# 20170628-03.net
KiCad netlist of a schematic drawn in EAGLE
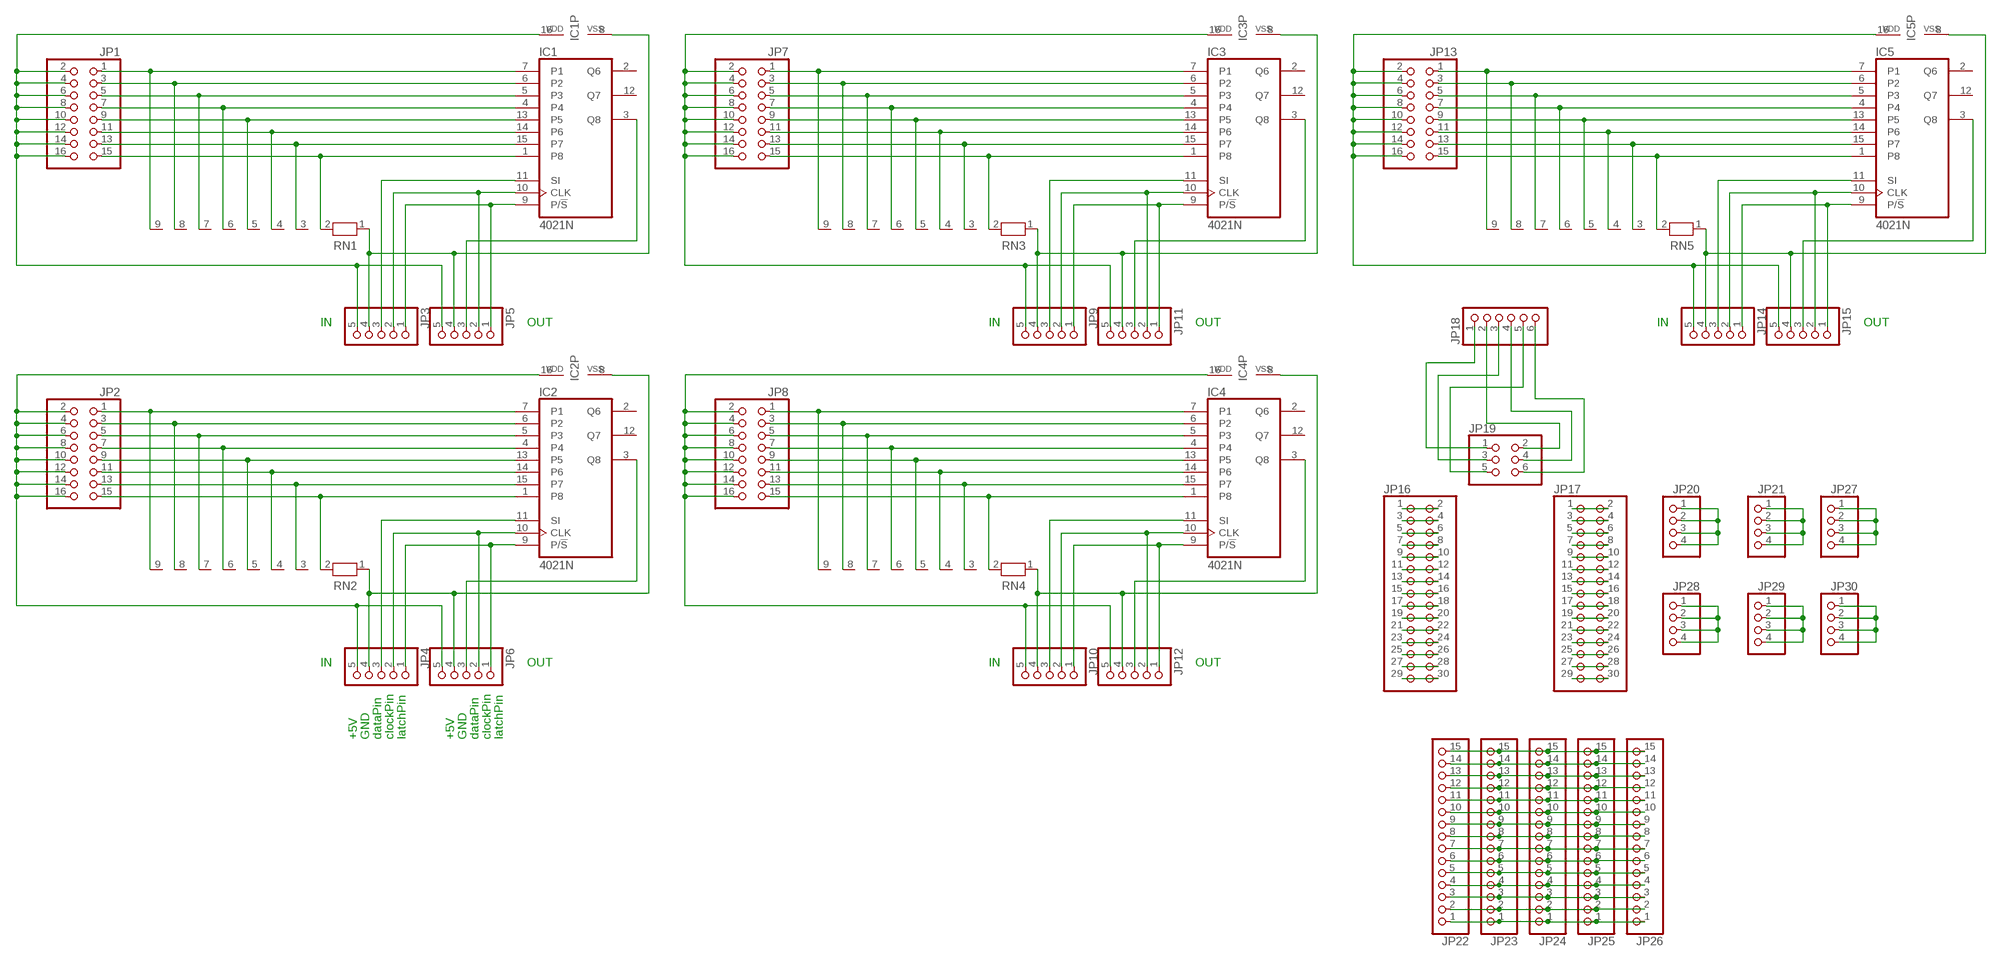
[diagram p0: schematic, sheet 1]

(export (version "E")
  (design (tool "Eeschema 10.0.6"))
  (components
    (comp (ref "IC1")
      (value "4021N")
      (footprint "eagle-import:DIL16")
      (libsource (lib "eagle-import") (part "4021N"))
    )
    (comp (ref "IC2")
      (value "4021N")
      (footprint "eagle-import:DIL16")
      (libsource (lib "eagle-import") (part "4021N"))
    )
    (comp (ref "IC3")
      (value "4021N")
      (footprint "eagle-import:DIL16")
      (libsource (lib "eagle-import") (part "4021N"))
    )
    (comp (ref "IC4")
      (value "4021N")
      (footprint "eagle-import:DIL16")
      (libsource (lib "eagle-import") (part "4021N"))
    )
    (comp (ref "IC5")
      (value "4021N")
      (footprint "eagle-import:DIL16")
      (libsource (lib "eagle-import") (part "4021N"))
    )
    (comp (ref "JP1")
      (value "PINHD-2X8")
      (footprint "eagle-import:2X08")
      (libsource (lib "eagle-import") (part "PINHD-2X8"))
    )
    (comp (ref "JP2")
      (value "PINHD-2X8")
      (footprint "eagle-import:2X08")
      (libsource (lib "eagle-import") (part "PINHD-2X8"))
    )
    (comp (ref "JP3")
      (value "PINHD-1X5")
      (footprint "eagle-import:1X05")
      (libsource (lib "eagle-import") (part "PINHD-1X5"))
    )
    (comp (ref "JP4")
      (value "PINHD-1X5")
      (footprint "eagle-import:1X05")
      (libsource (lib "eagle-import") (part "PINHD-1X5"))
    )
    (comp (ref "JP5")
      (value "PINHD-1X5")
      (footprint "eagle-import:1X05")
      (libsource (lib "eagle-import") (part "PINHD-1X5"))
    )
    (comp (ref "JP6")
      (value "PINHD-1X5")
      (footprint "eagle-import:1X05")
      (libsource (lib "eagle-import") (part "PINHD-1X5"))
    )
    (comp (ref "JP7")
      (value "PINHD-2X8")
      (footprint "eagle-import:2X08")
      (libsource (lib "eagle-import") (part "PINHD-2X8"))
    )
    (comp (ref "JP8")
      (value "PINHD-2X8")
      (footprint "eagle-import:2X08")
      (libsource (lib "eagle-import") (part "PINHD-2X8"))
    )
    (comp (ref "JP9")
      (value "PINHD-1X5")
      (footprint "eagle-import:1X05")
      (libsource (lib "eagle-import") (part "PINHD-1X5"))
    )
    (comp (ref "JP10")
      (value "PINHD-1X5")
      (footprint "eagle-import:1X05")
      (libsource (lib "eagle-import") (part "PINHD-1X5"))
    )
    (comp (ref "JP11")
      (value "PINHD-1X5")
      (footprint "eagle-import:1X05")
      (libsource (lib "eagle-import") (part "PINHD-1X5"))
    )
    (comp (ref "JP12")
      (value "PINHD-1X5")
      (footprint "eagle-import:1X05")
      (libsource (lib "eagle-import") (part "PINHD-1X5"))
    )
    (comp (ref "JP13")
      (value "PINHD-2X8")
      (footprint "eagle-import:2X08")
      (libsource (lib "eagle-import") (part "PINHD-2X8"))
    )
    (comp (ref "JP14")
      (value "PINHD-1X5")
      (footprint "eagle-import:1X05")
      (libsource (lib "eagle-import") (part "PINHD-1X5"))
    )
    (comp (ref "JP15")
      (value "PINHD-1X5")
      (footprint "eagle-import:1X05")
      (libsource (lib "eagle-import") (part "PINHD-1X5"))
    )
    (comp (ref "JP16")
      (value "PINHD-2X15")
      (footprint "eagle-import:2X15")
      (libsource (lib "eagle-import") (part "PINHD-2X15"))
    )
    (comp (ref "JP17")
      (value "PINHD-2X15")
      (footprint "eagle-import:2X15")
      (libsource (lib "eagle-import") (part "PINHD-2X15"))
    )
    (comp (ref "JP18")
      (value "PINHD-1X6")
      (footprint "eagle-import:1X06")
      (libsource (lib "eagle-import") (part "PINHD-1X6"))
    )
    (comp (ref "JP19")
      (value "PINHD-2X3")
      (footprint "eagle-import:2X03")
      (libsource (lib "eagle-import") (part "PINHD-2X3"))
    )
    (comp (ref "JP20")
      (value "PINHD-1X4")
      (footprint "eagle-import:1X04")
      (libsource (lib "eagle-import") (part "PINHD-1X4"))
    )
    (comp (ref "JP21")
      (value "PINHD-1X4")
      (footprint "eagle-import:1X04")
      (libsource (lib "eagle-import") (part "PINHD-1X4"))
    )
    (comp (ref "JP22")
      (value "PINHD-1X15")
      (footprint "eagle-import:1X15")
      (libsource (lib "eagle-import") (part "PINHD-1X15"))
    )
    (comp (ref "JP23")
      (value "PINHD-1X15")
      (footprint "eagle-import:1X15")
      (libsource (lib "eagle-import") (part "PINHD-1X15"))
    )
    (comp (ref "JP24")
      (value "PINHD-1X15")
      (footprint "eagle-import:1X15")
      (libsource (lib "eagle-import") (part "PINHD-1X15"))
    )
    (comp (ref "JP25")
      (value "PINHD-1X15")
      (footprint "eagle-import:1X15")
      (libsource (lib "eagle-import") (part "PINHD-1X15"))
    )
    (comp (ref "JP26")
      (value "PINHD-1X15")
      (footprint "eagle-import:1X15")
      (libsource (lib "eagle-import") (part "PINHD-1X15"))
    )
    (comp (ref "JP27")
      (value "PINHD-1X4")
      (footprint "eagle-import:1X04")
      (libsource (lib "eagle-import") (part "PINHD-1X4"))
    )
    (comp (ref "JP28")
      (value "PINHD-1X4")
      (footprint "eagle-import:1X04")
      (libsource (lib "eagle-import") (part "PINHD-1X4"))
    )
    (comp (ref "JP29")
      (value "PINHD-1X4")
      (footprint "eagle-import:1X04")
      (libsource (lib "eagle-import") (part "PINHD-1X4"))
    )
    (comp (ref "JP30")
      (value "PINHD-1X4")
      (footprint "eagle-import:1X04")
      (libsource (lib "eagle-import") (part "PINHD-1X4"))
    )
    (comp (ref "RN1")
      (value "RN08")
      (footprint "eagle-import:RN-9")
      (libsource (lib "eagle-import") (part "RN08"))
    )
    (comp (ref "RN2")
      (value "RN08")
      (footprint "eagle-import:RN-9")
      (libsource (lib "eagle-import") (part "RN08"))
    )
    (comp (ref "RN3")
      (value "RN08")
      (footprint "eagle-import:RN-9")
      (libsource (lib "eagle-import") (part "RN08"))
    )
    (comp (ref "RN4")
      (value "RN08")
      (footprint "eagle-import:RN-9")
      (libsource (lib "eagle-import") (part "RN08"))
    )
    (comp (ref "RN5")
      (value "RN08")
      (footprint "eagle-import:RN-9")
      (libsource (lib "eagle-import") (part "RN08"))
    )
  )
  (nets
    (net (code "1") (name "Net-(IC1A-CLK)") (class "Default")
      (node (ref "IC1") (pin "10") (pinfunction "CLK_10") (pintype "input"))
      (node (ref "JP3") (pin "2") (pinfunction "2_2") (pintype "passive"))
      (node (ref "JP5") (pin "2") (pinfunction "2_2") (pintype "passive"))
    )
    (net (code "2") (name "Net-(IC1A-P1)") (class "Default")
      (node (ref "IC1") (pin "7") (pinfunction "P1_7") (pintype "input"))
      (node (ref "JP1") (pin "1") (pinfunction "1_1") (pintype "passive"))
      (node (ref "RN1") (pin "9") (pinfunction "9_9") (pintype "passive"))
    )
    (net (code "3") (name "Net-(IC1A-P2)") (class "Default")
      (node (ref "IC1") (pin "6") (pinfunction "P2_6") (pintype "input"))
      (node (ref "JP1") (pin "3") (pinfunction "3_3") (pintype "passive"))
      (node (ref "RN1") (pin "8") (pinfunction "8_8") (pintype "passive"))
    )
    (net (code "4") (name "Net-(IC1A-P3)") (class "Default")
      (node (ref "IC1") (pin "5") (pinfunction "P3_5") (pintype "input"))
      (node (ref "JP1") (pin "5") (pinfunction "5_5") (pintype "passive"))
      (node (ref "RN1") (pin "7") (pinfunction "7_7") (pintype "passive"))
    )
    (net (code "5") (name "Net-(IC1A-P4)") (class "Default")
      (node (ref "IC1") (pin "4") (pinfunction "P4_4") (pintype "input"))
      (node (ref "JP1") (pin "7") (pinfunction "7_7") (pintype "passive"))
      (node (ref "RN1") (pin "6") (pinfunction "6_6") (pintype "passive"))
    )
    (net (code "6") (name "Net-(IC1A-P5)") (class "Default")
      (node (ref "IC1") (pin "13") (pinfunction "P5_13") (pintype "input"))
      (node (ref "JP1") (pin "9") (pinfunction "9_9") (pintype "passive"))
      (node (ref "RN1") (pin "5") (pinfunction "5_5") (pintype "passive"))
    )
    (net (code "7") (name "Net-(IC1A-P6)") (class "Default")
      (node (ref "IC1") (pin "14") (pinfunction "P6_14") (pintype "input"))
      (node (ref "JP1") (pin "11") (pinfunction "11_11") (pintype "passive"))
      (node (ref "RN1") (pin "4") (pinfunction "4_4") (pintype "passive"))
    )
    (net (code "8") (name "Net-(IC1A-P7)") (class "Default")
      (node (ref "IC1") (pin "15") (pinfunction "P7_15") (pintype "input"))
      (node (ref "JP1") (pin "13") (pinfunction "13_13") (pintype "passive"))
      (node (ref "RN1") (pin "3") (pinfunction "3_3") (pintype "passive"))
    )
    (net (code "9") (name "Net-(IC1A-P8)") (class "Default")
      (node (ref "IC1") (pin "1") (pinfunction "P8_1") (pintype "input"))
      (node (ref "JP1") (pin "15") (pinfunction "15_15") (pintype "passive"))
      (node (ref "RN1") (pin "2") (pinfunction "2_2") (pintype "passive"))
    )
    (net (code "10") (name "Net-(IC1A-P{slash}~{S})") (class "Default")
      (node (ref "IC1") (pin "9") (pinfunction "P/~{S}_9") (pintype "input"))
      (node (ref "JP3") (pin "1") (pinfunction "1_1") (pintype "passive"))
      (node (ref "JP5") (pin "1") (pinfunction "1_1") (pintype "passive"))
    )
    (net (code "11") (name "Net-(IC1A-Q8)") (class "Default")
      (node (ref "IC1") (pin "3") (pinfunction "Q8_3") (pintype "output"))
      (node (ref "JP5") (pin "3") (pinfunction "3_3") (pintype "passive"))
    )
    (net (code "12") (name "Net-(IC1A-SI)") (class "Default")
      (node (ref "IC1") (pin "11") (pinfunction "SI_11") (pintype "input"))
      (node (ref "JP3") (pin "3") (pinfunction "3_3") (pintype "passive"))
    )
    (net (code "13") (name "Net-(IC1B-VDD)") (class "Default")
      (node (ref "IC1") (pin "16") (pinfunction "VDD_16") (pintype "power_in"))
      (node (ref "JP1") (pin "10") (pinfunction "10_10") (pintype "passive"))
      (node (ref "JP1") (pin "12") (pinfunction "12_12") (pintype "passive"))
      (node (ref "JP1") (pin "14") (pinfunction "14_14") (pintype "passive"))
      (node (ref "JP1") (pin "16") (pinfunction "16_16") (pintype "passive"))
      (node (ref "JP1") (pin "2") (pinfunction "2_2") (pintype "passive"))
      (node (ref "JP1") (pin "4") (pinfunction "4_4") (pintype "passive"))
      (node (ref "JP1") (pin "6") (pinfunction "6_6") (pintype "passive"))
      (node (ref "JP1") (pin "8") (pinfunction "8_8") (pintype "passive"))
      (node (ref "JP3") (pin "5") (pinfunction "5_5") (pintype "passive"))
      (node (ref "JP5") (pin "5") (pinfunction "5_5") (pintype "passive"))
    )
    (net (code "14") (name "Net-(IC1B-VSS)") (class "Default")
      (node (ref "IC1") (pin "8") (pinfunction "VSS_8") (pintype "power_in"))
      (node (ref "JP3") (pin "4") (pinfunction "4_4") (pintype "passive"))
      (node (ref "JP5") (pin "4") (pinfunction "4_4") (pintype "passive"))
      (node (ref "RN1") (pin "1") (pinfunction "1_1") (pintype "passive"))
    )
    (net (code "15") (name "Net-(IC2A-CLK)") (class "Default")
      (node (ref "IC2") (pin "10") (pinfunction "CLK_10") (pintype "input"))
      (node (ref "JP4") (pin "2") (pinfunction "2_2") (pintype "passive"))
      (node (ref "JP6") (pin "2") (pinfunction "2_2") (pintype "passive"))
    )
    (net (code "16") (name "Net-(IC2A-P1)") (class "Default")
      (node (ref "IC2") (pin "7") (pinfunction "P1_7") (pintype "input"))
      (node (ref "JP2") (pin "1") (pinfunction "1_1") (pintype "passive"))
      (node (ref "RN2") (pin "9") (pinfunction "9_9") (pintype "passive"))
    )
    (net (code "17") (name "Net-(IC2A-P2)") (class "Default")
      (node (ref "IC2") (pin "6") (pinfunction "P2_6") (pintype "input"))
      (node (ref "JP2") (pin "3") (pinfunction "3_3") (pintype "passive"))
      (node (ref "RN2") (pin "8") (pinfunction "8_8") (pintype "passive"))
    )
    (net (code "18") (name "Net-(IC2A-P3)") (class "Default")
      (node (ref "IC2") (pin "5") (pinfunction "P3_5") (pintype "input"))
      (node (ref "JP2") (pin "5") (pinfunction "5_5") (pintype "passive"))
      (node (ref "RN2") (pin "7") (pinfunction "7_7") (pintype "passive"))
    )
    (net (code "19") (name "Net-(IC2A-P4)") (class "Default")
      (node (ref "IC2") (pin "4") (pinfunction "P4_4") (pintype "input"))
      (node (ref "JP2") (pin "7") (pinfunction "7_7") (pintype "passive"))
      (node (ref "RN2") (pin "6") (pinfunction "6_6") (pintype "passive"))
    )
    (net (code "20") (name "Net-(IC2A-P5)") (class "Default")
      (node (ref "IC2") (pin "13") (pinfunction "P5_13") (pintype "input"))
      (node (ref "JP2") (pin "9") (pinfunction "9_9") (pintype "passive"))
      (node (ref "RN2") (pin "5") (pinfunction "5_5") (pintype "passive"))
    )
    (net (code "21") (name "Net-(IC2A-P6)") (class "Default")
      (node (ref "IC2") (pin "14") (pinfunction "P6_14") (pintype "input"))
      (node (ref "JP2") (pin "11") (pinfunction "11_11") (pintype "passive"))
      (node (ref "RN2") (pin "4") (pinfunction "4_4") (pintype "passive"))
    )
    (net (code "22") (name "Net-(IC2A-P7)") (class "Default")
      (node (ref "IC2") (pin "15") (pinfunction "P7_15") (pintype "input"))
      (node (ref "JP2") (pin "13") (pinfunction "13_13") (pintype "passive"))
      (node (ref "RN2") (pin "3") (pinfunction "3_3") (pintype "passive"))
    )
    (net (code "23") (name "Net-(IC2A-P8)") (class "Default")
      (node (ref "IC2") (pin "1") (pinfunction "P8_1") (pintype "input"))
      (node (ref "JP2") (pin "15") (pinfunction "15_15") (pintype "passive"))
      (node (ref "RN2") (pin "2") (pinfunction "2_2") (pintype "passive"))
    )
    (net (code "24") (name "Net-(IC2A-P{slash}~{S})") (class "Default")
      (node (ref "IC2") (pin "9") (pinfunction "P/~{S}_9") (pintype "input"))
      (node (ref "JP4") (pin "1") (pinfunction "1_1") (pintype "passive"))
      (node (ref "JP6") (pin "1") (pinfunction "1_1") (pintype "passive"))
    )
    (net (code "25") (name "Net-(IC2A-Q8)") (class "Default")
      (node (ref "IC2") (pin "3") (pinfunction "Q8_3") (pintype "output"))
      (node (ref "JP6") (pin "3") (pinfunction "3_3") (pintype "passive"))
    )
    (net (code "26") (name "Net-(IC2A-SI)") (class "Default")
      (node (ref "IC2") (pin "11") (pinfunction "SI_11") (pintype "input"))
      (node (ref "JP4") (pin "3") (pinfunction "3_3") (pintype "passive"))
    )
    (net (code "27") (name "Net-(IC2B-VDD)") (class "Default")
      (node (ref "IC2") (pin "16") (pinfunction "VDD_16") (pintype "power_in"))
      (node (ref "JP2") (pin "10") (pinfunction "10_10") (pintype "passive"))
      (node (ref "JP2") (pin "12") (pinfunction "12_12") (pintype "passive"))
      (node (ref "JP2") (pin "14") (pinfunction "14_14") (pintype "passive"))
      (node (ref "JP2") (pin "16") (pinfunction "16_16") (pintype "passive"))
      (node (ref "JP2") (pin "2") (pinfunction "2_2") (pintype "passive"))
      (node (ref "JP2") (pin "4") (pinfunction "4_4") (pintype "passive"))
      (node (ref "JP2") (pin "6") (pinfunction "6_6") (pintype "passive"))
      (node (ref "JP2") (pin "8") (pinfunction "8_8") (pintype "passive"))
      (node (ref "JP4") (pin "5") (pinfunction "5_5") (pintype "passive"))
      (node (ref "JP6") (pin "5") (pinfunction "5_5") (pintype "passive"))
    )
    (net (code "28") (name "Net-(IC2B-VSS)") (class "Default")
      (node (ref "IC2") (pin "8") (pinfunction "VSS_8") (pintype "power_in"))
      (node (ref "JP4") (pin "4") (pinfunction "4_4") (pintype "passive"))
      (node (ref "JP6") (pin "4") (pinfunction "4_4") (pintype "passive"))
      (node (ref "RN2") (pin "1") (pinfunction "1_1") (pintype "passive"))
    )
    (net (code "29") (name "Net-(IC3A-CLK)") (class "Default")
      (node (ref "IC3") (pin "10") (pinfunction "CLK_10") (pintype "input"))
      (node (ref "JP11") (pin "2") (pinfunction "2_2") (pintype "passive"))
      (node (ref "JP9") (pin "2") (pinfunction "2_2") (pintype "passive"))
    )
    (net (code "30") (name "Net-(IC3A-P1)") (class "Default")
      (node (ref "IC3") (pin "7") (pinfunction "P1_7") (pintype "input"))
      (node (ref "JP7") (pin "1") (pinfunction "1_1") (pintype "passive"))
      (node (ref "RN3") (pin "9") (pinfunction "9_9") (pintype "passive"))
    )
    (net (code "31") (name "Net-(IC3A-P2)") (class "Default")
      (node (ref "IC3") (pin "6") (pinfunction "P2_6") (pintype "input"))
      (node (ref "JP7") (pin "3") (pinfunction "3_3") (pintype "passive"))
      (node (ref "RN3") (pin "8") (pinfunction "8_8") (pintype "passive"))
    )
    (net (code "32") (name "Net-(IC3A-P3)") (class "Default")
      (node (ref "IC3") (pin "5") (pinfunction "P3_5") (pintype "input"))
      (node (ref "JP7") (pin "5") (pinfunction "5_5") (pintype "passive"))
      (node (ref "RN3") (pin "7") (pinfunction "7_7") (pintype "passive"))
    )
    (net (code "33") (name "Net-(IC3A-P4)") (class "Default")
      (node (ref "IC3") (pin "4") (pinfunction "P4_4") (pintype "input"))
      (node (ref "JP7") (pin "7") (pinfunction "7_7") (pintype "passive"))
      (node (ref "RN3") (pin "6") (pinfunction "6_6") (pintype "passive"))
    )
    (net (code "34") (name "Net-(IC3A-P5)") (class "Default")
      (node (ref "IC3") (pin "13") (pinfunction "P5_13") (pintype "input"))
      (node (ref "JP7") (pin "9") (pinfunction "9_9") (pintype "passive"))
      (node (ref "RN3") (pin "5") (pinfunction "5_5") (pintype "passive"))
    )
    (net (code "35") (name "Net-(IC3A-P6)") (class "Default")
      (node (ref "IC3") (pin "14") (pinfunction "P6_14") (pintype "input"))
      (node (ref "JP7") (pin "11") (pinfunction "11_11") (pintype "passive"))
      (node (ref "RN3") (pin "4") (pinfunction "4_4") (pintype "passive"))
    )
    (net (code "36") (name "Net-(IC3A-P7)") (class "Default")
      (node (ref "IC3") (pin "15") (pinfunction "P7_15") (pintype "input"))
      (node (ref "JP7") (pin "13") (pinfunction "13_13") (pintype "passive"))
      (node (ref "RN3") (pin "3") (pinfunction "3_3") (pintype "passive"))
    )
    (net (code "37") (name "Net-(IC3A-P8)") (class "Default")
      (node (ref "IC3") (pin "1") (pinfunction "P8_1") (pintype "input"))
      (node (ref "JP7") (pin "15") (pinfunction "15_15") (pintype "passive"))
      (node (ref "RN3") (pin "2") (pinfunction "2_2") (pintype "passive"))
    )
    (net (code "38") (name "Net-(IC3A-P{slash}~{S})") (class "Default")
      (node (ref "IC3") (pin "9") (pinfunction "P/~{S}_9") (pintype "input"))
      (node (ref "JP11") (pin "1") (pinfunction "1_1") (pintype "passive"))
      (node (ref "JP9") (pin "1") (pinfunction "1_1") (pintype "passive"))
    )
    (net (code "39") (name "Net-(IC3A-Q8)") (class "Default")
      (node (ref "IC3") (pin "3") (pinfunction "Q8_3") (pintype "output"))
      (node (ref "JP11") (pin "3") (pinfunction "3_3") (pintype "passive"))
    )
    (net (code "40") (name "Net-(IC3A-SI)") (class "Default")
      (node (ref "IC3") (pin "11") (pinfunction "SI_11") (pintype "input"))
      (node (ref "JP9") (pin "3") (pinfunction "3_3") (pintype "passive"))
    )
    (net (code "41") (name "Net-(IC3B-VDD)") (class "Default")
      (node (ref "IC3") (pin "16") (pinfunction "VDD_16") (pintype "power_in"))
      (node (ref "JP11") (pin "5") (pinfunction "5_5") (pintype "passive"))
      (node (ref "JP7") (pin "10") (pinfunction "10_10") (pintype "passive"))
      (node (ref "JP7") (pin "12") (pinfunction "12_12") (pintype "passive"))
      (node (ref "JP7") (pin "14") (pinfunction "14_14") (pintype "passive"))
      (node (ref "JP7") (pin "16") (pinfunction "16_16") (pintype "passive"))
      (node (ref "JP7") (pin "2") (pinfunction "2_2") (pintype "passive"))
      (node (ref "JP7") (pin "4") (pinfunction "4_4") (pintype "passive"))
      (node (ref "JP7") (pin "6") (pinfunction "6_6") (pintype "passive"))
      (node (ref "JP7") (pin "8") (pinfunction "8_8") (pintype "passive"))
      (node (ref "JP9") (pin "5") (pinfunction "5_5") (pintype "passive"))
    )
    (net (code "42") (name "Net-(IC3B-VSS)") (class "Default")
      (node (ref "IC3") (pin "8") (pinfunction "VSS_8") (pintype "power_in"))
      (node (ref "JP11") (pin "4") (pinfunction "4_4") (pintype "passive"))
      (node (ref "JP9") (pin "4") (pinfunction "4_4") (pintype "passive"))
      (node (ref "RN3") (pin "1") (pinfunction "1_1") (pintype "passive"))
    )
    (net (code "43") (name "Net-(IC4A-CLK)") (class "Default")
      (node (ref "IC4") (pin "10") (pinfunction "CLK_10") (pintype "input"))
      (node (ref "JP10") (pin "2") (pinfunction "2_2") (pintype "passive"))
      (node (ref "JP12") (pin "2") (pinfunction "2_2") (pintype "passive"))
    )
    (net (code "44") (name "Net-(IC4A-P1)") (class "Default")
      (node (ref "IC4") (pin "7") (pinfunction "P1_7") (pintype "input"))
      (node (ref "JP8") (pin "1") (pinfunction "1_1") (pintype "passive"))
      (node (ref "RN4") (pin "9") (pinfunction "9_9") (pintype "passive"))
    )
    (net (code "45") (name "Net-(IC4A-P2)") (class "Default")
      (node (ref "IC4") (pin "6") (pinfunction "P2_6") (pintype "input"))
      (node (ref "JP8") (pin "3") (pinfunction "3_3") (pintype "passive"))
      (node (ref "RN4") (pin "8") (pinfunction "8_8") (pintype "passive"))
    )
    (net (code "46") (name "Net-(IC4A-P3)") (class "Default")
      (node (ref "IC4") (pin "5") (pinfunction "P3_5") (pintype "input"))
      (node (ref "JP8") (pin "5") (pinfunction "5_5") (pintype "passive"))
      (node (ref "RN4") (pin "7") (pinfunction "7_7") (pintype "passive"))
    )
    (net (code "47") (name "Net-(IC4A-P4)") (class "Default")
      (node (ref "IC4") (pin "4") (pinfunction "P4_4") (pintype "input"))
      (node (ref "JP8") (pin "7") (pinfunction "7_7") (pintype "passive"))
      (node (ref "RN4") (pin "6") (pinfunction "6_6") (pintype "passive"))
    )
    (net (code "48") (name "Net-(IC4A-P5)") (class "Default")
      (node (ref "IC4") (pin "13") (pinfunction "P5_13") (pintype "input"))
      (node (ref "JP8") (pin "9") (pinfunction "9_9") (pintype "passive"))
      (node (ref "RN4") (pin "5") (pinfunction "5_5") (pintype "passive"))
    )
    (net (code "49") (name "Net-(IC4A-P6)") (class "Default")
      (node (ref "IC4") (pin "14") (pinfunction "P6_14") (pintype "input"))
      (node (ref "JP8") (pin "11") (pinfunction "11_11") (pintype "passive"))
      (node (ref "RN4") (pin "4") (pinfunction "4_4") (pintype "passive"))
    )
    (net (code "50") (name "Net-(IC4A-P7)") (class "Default")
      (node (ref "IC4") (pin "15") (pinfunction "P7_15") (pintype "input"))
      (node (ref "JP8") (pin "13") (pinfunction "13_13") (pintype "passive"))
      (node (ref "RN4") (pin "3") (pinfunction "3_3") (pintype "passive"))
    )
    (net (code "51") (name "Net-(IC4A-P8)") (class "Default")
      (node (ref "IC4") (pin "1") (pinfunction "P8_1") (pintype "input"))
      (node (ref "JP8") (pin "15") (pinfunction "15_15") (pintype "passive"))
      (node (ref "RN4") (pin "2") (pinfunction "2_2") (pintype "passive"))
    )
    (net (code "52") (name "Net-(IC4A-P{slash}~{S})") (class "Default")
      (node (ref "IC4") (pin "9") (pinfunction "P/~{S}_9") (pintype "input"))
      (node (ref "JP10") (pin "1") (pinfunction "1_1") (pintype "passive"))
      (node (ref "JP12") (pin "1") (pinfunction "1_1") (pintype "passive"))
    )
    (net (code "53") (name "Net-(IC4A-Q8)") (class "Default")
      (node (ref "IC4") (pin "3") (pinfunction "Q8_3") (pintype "output"))
      (node (ref "JP12") (pin "3") (pinfunction "3_3") (pintype "passive"))
    )
    (net (code "54") (name "Net-(IC4A-SI)") (class "Default")
      (node (ref "IC4") (pin "11") (pinfunction "SI_11") (pintype "input"))
      (node (ref "JP10") (pin "3") (pinfunction "3_3") (pintype "passive"))
    )
    (net (code "55") (name "Net-(IC4B-VDD)") (class "Default")
      (node (ref "IC4") (pin "16") (pinfunction "VDD_16") (pintype "power_in"))
      (node (ref "JP10") (pin "5") (pinfunction "5_5") (pintype "passive"))
      (node (ref "JP12") (pin "5") (pinfunction "5_5") (pintype "passive"))
      (node (ref "JP8") (pin "10") (pinfunction "10_10") (pintype "passive"))
      (node (ref "JP8") (pin "12") (pinfunction "12_12") (pintype "passive"))
      (node (ref "JP8") (pin "14") (pinfunction "14_14") (pintype "passive"))
      (node (ref "JP8") (pin "16") (pinfunction "16_16") (pintype "passive"))
      (node (ref "JP8") (pin "2") (pinfunction "2_2") (pintype "passive"))
      (node (ref "JP8") (pin "4") (pinfunction "4_4") (pintype "passive"))
      (node (ref "JP8") (pin "6") (pinfunction "6_6") (pintype "passive"))
      (node (ref "JP8") (pin "8") (pinfunction "8_8") (pintype "passive"))
    )
    (net (code "56") (name "Net-(IC4B-VSS)") (class "Default")
      (node (ref "IC4") (pin "8") (pinfunction "VSS_8") (pintype "power_in"))
      (node (ref "JP10") (pin "4") (pinfunction "4_4") (pintype "passive"))
      (node (ref "JP12") (pin "4") (pinfunction "4_4") (pintype "passive"))
      (node (ref "RN4") (pin "1") (pinfunction "1_1") (pintype "passive"))
    )
    (net (code "57") (name "Net-(IC5A-CLK)") (class "Default")
      (node (ref "IC5") (pin "10") (pinfunction "CLK_10") (pintype "input"))
      (node (ref "JP14") (pin "2") (pinfunction "2_2") (pintype "passive"))
      (node (ref "JP15") (pin "2") (pinfunction "2_2") (pintype "passive"))
    )
    (net (code "58") (name "Net-(IC5A-P1)") (class "Default")
      (node (ref "IC5") (pin "7") (pinfunction "P1_7") (pintype "input"))
      (node (ref "JP13") (pin "1") (pinfunction "1_1") (pintype "passive"))
      (node (ref "RN5") (pin "9") (pinfunction "9_9") (pintype "passive"))
    )
    (net (code "59") (name "Net-(IC5A-P2)") (class "Default")
      (node (ref "IC5") (pin "6") (pinfunction "P2_6") (pintype "input"))
      (node (ref "JP13") (pin "3") (pinfunction "3_3") (pintype "passive"))
      (node (ref "RN5") (pin "8") (pinfunction "8_8") (pintype "passive"))
    )
    (net (code "60") (name "Net-(IC5A-P3)") (class "Default")
      (node (ref "IC5") (pin "5") (pinfunction "P3_5") (pintype "input"))
      (node (ref "JP13") (pin "5") (pinfunction "5_5") (pintype "passive"))
      (node (ref "RN5") (pin "7") (pinfunction "7_7") (pintype "passive"))
    )
    (net (code "61") (name "Net-(IC5A-P4)") (class "Default")
      (node (ref "IC5") (pin "4") (pinfunction "P4_4") (pintype "input"))
      (node (ref "JP13") (pin "7") (pinfunction "7_7") (pintype "passive"))
      (node (ref "RN5") (pin "6") (pinfunction "6_6") (pintype "passive"))
    )
    (net (code "62") (name "Net-(IC5A-P5)") (class "Default")
      (node (ref "IC5") (pin "13") (pinfunction "P5_13") (pintype "input"))
      (node (ref "JP13") (pin "9") (pinfunction "9_9") (pintype "passive"))
      (node (ref "RN5") (pin "5") (pinfunction "5_5") (pintype "passive"))
    )
    (net (code "63") (name "Net-(IC5A-P6)") (class "Default")
      (node (ref "IC5") (pin "14") (pinfunction "P6_14") (pintype "input"))
      (node (ref "JP13") (pin "11") (pinfunction "11_11") (pintype "passive"))
      (node (ref "RN5") (pin "4") (pinfunction "4_4") (pintype "passive"))
    )
    (net (code "64") (name "Net-(IC5A-P7)") (class "Default")
      (node (ref "IC5") (pin "15") (pinfunction "P7_15") (pintype "input"))
      (node (ref "JP13") (pin "13") (pinfunction "13_13") (pintype "passive"))
      (node (ref "RN5") (pin "3") (pinfunction "3_3") (pintype "passive"))
    )
    (net (code "65") (name "Net-(IC5A-P8)") (class "Default")
      (node (ref "IC5") (pin "1") (pinfunction "P8_1") (pintype "input"))
      (node (ref "JP13") (pin "15") (pinfunction "15_15") (pintype "passive"))
      (node (ref "RN5") (pin "2") (pinfunction "2_2") (pintype "passive"))
    )
    (net (code "66") (name "Net-(IC5A-P{slash}~{S})") (class "Default")
      (node (ref "IC5") (pin "9") (pinfunction "P/~{S}_9") (pintype "input"))
      (node (ref "JP14") (pin "1") (pinfunction "1_1") (pintype "passive"))
      (node (ref "JP15") (pin "1") (pinfunction "1_1") (pintype "passive"))
    )
    (net (code "67") (name "Net-(IC5A-Q8)") (class "Default")
      (node (ref "IC5") (pin "3") (pinfunction "Q8_3") (pintype "output"))
      (node (ref "JP15") (pin "3") (pinfunction "3_3") (pintype "passive"))
    )
    (net (code "68") (name "Net-(IC5A-SI)") (class "Default")
      (node (ref "IC5") (pin "11") (pinfunction "SI_11") (pintype "input"))
      (node (ref "JP14") (pin "3") (pinfunction "3_3") (pintype "passive"))
    )
    (net (code "69") (name "Net-(IC5B-VDD)") (class "Default")
      (node (ref "IC5") (pin "16") (pinfunction "VDD_16") (pintype "power_in"))
      (node (ref "JP13") (pin "10") (pinfunction "10_10") (pintype "passive"))
      (node (ref "JP13") (pin "12") (pinfunction "12_12") (pintype "passive"))
      (node (ref "JP13") (pin "14") (pinfunction "14_14") (pintype "passive"))
      (node (ref "JP13") (pin "16") (pinfunction "16_16") (pintype "passive"))
      (node (ref "JP13") (pin "2") (pinfunction "2_2") (pintype "passive"))
      (node (ref "JP13") (pin "4") (pinfunction "4_4") (pintype "passive"))
      (node (ref "JP13") (pin "6") (pinfunction "6_6") (pintype "passive"))
      (node (ref "JP13") (pin "8") (pinfunction "8_8") (pintype "passive"))
      (node (ref "JP14") (pin "5") (pinfunction "5_5") (pintype "passive"))
      (node (ref "JP15") (pin "5") (pinfunction "5_5") (pintype "passive"))
    )
    (net (code "70") (name "Net-(IC5B-VSS)") (class "Default")
      (node (ref "IC5") (pin "8") (pinfunction "VSS_8") (pintype "power_in"))
      (node (ref "JP14") (pin "4") (pinfunction "4_4") (pintype "passive"))
      (node (ref "JP15") (pin "4") (pinfunction "4_4") (pintype "passive"))
      (node (ref "RN5") (pin "1") (pinfunction "1_1") (pintype "passive"))
    )
    (net (code "71") (name "Net-(JP16-Pad1)") (class "Default")
      (node (ref "JP16") (pin "1") (pinfunction "1_1") (pintype "passive"))
      (node (ref "JP16") (pin "2") (pinfunction "2_2") (pintype "passive"))
    )
    (net (code "72") (name "Net-(JP16-Pad3)") (class "Default")
      (node (ref "JP16") (pin "3") (pinfunction "3_3") (pintype "passive"))
      (node (ref "JP16") (pin "4") (pinfunction "4_4") (pintype "passive"))
    )
    (net (code "73") (name "Net-(JP16-Pad5)") (class "Default")
      (node (ref "JP16") (pin "5") (pinfunction "5_5") (pintype "passive"))
      (node (ref "JP16") (pin "6") (pinfunction "6_6") (pintype "passive"))
    )
    (net (code "74") (name "Net-(JP16-Pad7)") (class "Default")
      (node (ref "JP16") (pin "7") (pinfunction "7_7") (pintype "passive"))
      (node (ref "JP16") (pin "8") (pinfunction "8_8") (pintype "passive"))
    )
    (net (code "75") (name "Net-(JP16-Pad10)") (class "Default")
      (node (ref "JP16") (pin "10") (pinfunction "10_10") (pintype "passive"))
      (node (ref "JP16") (pin "9") (pinfunction "9_9") (pintype "passive"))
    )
    (net (code "76") (name "Net-(JP16-Pad11)") (class "Default")
      (node (ref "JP16") (pin "11") (pinfunction "11_11") (pintype "passive"))
      (node (ref "JP16") (pin "12") (pinfunction "12_12") (pintype "passive"))
    )
    (net (code "77") (name "Net-(JP16-Pad13)") (class "Default")
      (node (ref "JP16") (pin "13") (pinfunction "13_13") (pintype "passive"))
      (node (ref "JP16") (pin "14") (pinfunction "14_14") (pintype "passive"))
    )
    (net (code "78") (name "Net-(JP16-Pad15)") (class "Default")
      (node (ref "JP16") (pin "15") (pinfunction "15_15") (pintype "passive"))
      (node (ref "JP16") (pin "16") (pinfunction "16_16") (pintype "passive"))
    )
    (net (code "79") (name "Net-(JP16-Pad17)") (class "Default")
      (node (ref "JP16") (pin "17") (pinfunction "17_17") (pintype "passive"))
      (node (ref "JP16") (pin "18") (pinfunction "18_18") (pintype "passive"))
    )
    (net (code "80") (name "Net-(JP16-Pad19)") (class "Default")
      (node (ref "JP16") (pin "19") (pinfunction "19_19") (pintype "passive"))
      (node (ref "JP16") (pin "20") (pinfunction "20_20") (pintype "passive"))
    )
    (net (code "81") (name "Net-(JP16-Pad21)") (class "Default")
      (node (ref "JP16") (pin "21") (pinfunction "21_21") (pintype "passive"))
      (node (ref "JP16") (pin "22") (pinfunction "22_22") (pintype "passive"))
    )
    (net (code "82") (name "Net-(JP16-Pad23)") (class "Default")
      (node (ref "JP16") (pin "23") (pinfunction "23_23") (pintype "passive"))
      (node (ref "JP16") (pin "24") (pinfunction "24_24") (pintype "passive"))
    )
    (net (code "83") (name "Net-(JP16-Pad25)") (class "Default")
      (node (ref "JP16") (pin "25") (pinfunction "25_25") (pintype "passive"))
      (node (ref "JP16") (pin "26") (pinfunction "26_26") (pintype "passive"))
    )
    (net (code "84") (name "Net-(JP16-Pad27)") (class "Default")
      (node (ref "JP16") (pin "27") (pinfunction "27_27") (pintype "passive"))
      (node (ref "JP16") (pin "28") (pinfunction "28_28") (pintype "passive"))
    )
    (net (code "85") (name "Net-(JP16-Pad29)") (class "Default")
      (node (ref "JP16") (pin "29") (pinfunction "29_29") (pintype "passive"))
      (node (ref "JP16") (pin "30") (pinfunction "30_30") (pintype "passive"))
    )
    (net (code "86") (name "Net-(JP17-Pad1)") (class "Default")
      (node (ref "JP17") (pin "1") (pinfunction "1_1") (pintype "passive"))
      (node (ref "JP17") (pin "2") (pinfunction "2_2") (pintype "passive"))
    )
    (net (code "87") (name "Net-(JP17-Pad3)") (class "Default")
      (node (ref "JP17") (pin "3") (pinfunction "3_3") (pintype "passive"))
      (node (ref "JP17") (pin "4") (pinfunction "4_4") (pintype "passive"))
    )
    (net (code "88") (name "Net-(JP17-Pad5)") (class "Default")
      (node (ref "JP17") (pin "5") (pinfunction "5_5") (pintype "passive"))
      (node (ref "JP17") (pin "6") (pinfunction "6_6") (pintype "passive"))
    )
    (net (code "89") (name "Net-(JP17-Pad7)") (class "Default")
      (node (ref "JP17") (pin "7") (pinfunction "7_7") (pintype "passive"))
      (node (ref "JP17") (pin "8") (pinfunction "8_8") (pintype "passive"))
    )
    (net (code "90") (name "Net-(JP17-Pad10)") (class "Default")
      (node (ref "JP17") (pin "10") (pinfunction "10_10") (pintype "passive"))
      (node (ref "JP17") (pin "9") (pinfunction "9_9") (pintype "passive"))
    )
    (net (code "91") (name "Net-(JP17-Pad11)") (class "Default")
      (node (ref "JP17") (pin "11") (pinfunction "11_11") (pintype "passive"))
      (node (ref "JP17") (pin "12") (pinfunction "12_12") (pintype "passive"))
    )
    (net (code "92") (name "Net-(JP17-Pad13)") (class "Default")
      (node (ref "JP17") (pin "13") (pinfunction "13_13") (pintype "passive"))
      (node (ref "JP17") (pin "14") (pinfunction "14_14") (pintype "passive"))
    )
    (net (code "93") (name "Net-(JP17-Pad15)") (class "Default")
      (node (ref "JP17") (pin "15") (pinfunction "15_15") (pintype "passive"))
      (node (ref "JP17") (pin "16") (pinfunction "16_16") (pintype "passive"))
    )
    (net (code "94") (name "Net-(JP17-Pad17)") (class "Default")
      (node (ref "JP17") (pin "17") (pinfunction "17_17") (pintype "passive"))
      (node (ref "JP17") (pin "18") (pinfunction "18_18") (pintype "passive"))
    )
    (net (code "95") (name "Net-(JP17-Pad19)") (class "Default")
      (node (ref "JP17") (pin "19") (pinfunction "19_19") (pintype "passive"))
      (node (ref "JP17") (pin "20") (pinfunction "20_20") (pintype "passive"))
    )
    (net (code "96") (name "Net-(JP17-Pad21)") (class "Default")
      (node (ref "JP17") (pin "21") (pinfunction "21_21") (pintype "passive"))
      (node (ref "JP17") (pin "22") (pinfunction "22_22") (pintype "passive"))
    )
    (net (code "97") (name "Net-(JP17-Pad23)") (class "Default")
      (node (ref "JP17") (pin "23") (pinfunction "23_23") (pintype "passive"))
      (node (ref "JP17") (pin "24") (pinfunction "24_24") (pintype "passive"))
    )
    (net (code "98") (name "Net-(JP17-Pad25)") (class "Default")
      (node (ref "JP17") (pin "25") (pinfunction "25_25") (pintype "passive"))
      (node (ref "JP17") (pin "26") (pinfunction "26_26") (pintype "passive"))
    )
    (net (code "99") (name "Net-(JP17-Pad27)") (class "Default")
      (node (ref "JP17") (pin "27") (pinfunction "27_27") (pintype "passive"))
      (node (ref "JP17") (pin "28") (pinfunction "28_28") (pintype "passive"))
    )
    (net (code "100") (name "Net-(JP17-Pad29)") (class "Default")
      (node (ref "JP17") (pin "29") (pinfunction "29_29") (pintype "passive"))
      (node (ref "JP17") (pin "30") (pinfunction "30_30") (pintype "passive"))
    )
    (net (code "101") (name "Net-(JP18-Pad1)") (class "Default")
      (node (ref "JP18") (pin "1") (pinfunction "1_1") (pintype "passive"))
      (node (ref "JP19") (pin "1") (pinfunction "1_1") (pintype "passive"))
    )
    (net (code "102") (name "Net-(JP18-Pad2)") (class "Default")
      (node (ref "JP18") (pin "2") (pinfunction "2_2") (pintype "passive"))
      (node (ref "JP19") (pin "2") (pinfunction "2_2") (pintype "passive"))
    )
    (net (code "103") (name "Net-(JP18-Pad3)") (class "Default")
      (node (ref "JP18") (pin "3") (pinfunction "3_3") (pintype "passive"))
      (node (ref "JP19") (pin "3") (pinfunction "3_3") (pintype "passive"))
    )
    (net (code "104") (name "Net-(JP18-Pad4)") (class "Default")
      (node (ref "JP18") (pin "4") (pinfunction "4_4") (pintype "passive"))
      (node (ref "JP19") (pin "4") (pinfunction "4_4") (pintype "passive"))
    )
    (net (code "105") (name "Net-(JP18-Pad5)") (class "Default")
      (node (ref "JP18") (pin "5") (pinfunction "5_5") (pintype "passive"))
      (node (ref "JP19") (pin "5") (pinfunction "5_5") (pintype "passive"))
    )
    (net (code "106") (name "Net-(JP18-Pad6)") (class "Default")
      (node (ref "JP18") (pin "6") (pinfunction "6_6") (pintype "passive"))
      (node (ref "JP19") (pin "6") (pinfunction "6_6") (pintype "passive"))
    )
    (net (code "107") (name "Net-(JP20-Pad1)") (class "Default")
      (node (ref "JP20") (pin "1") (pinfunction "1_1") (pintype "passive"))
      (node (ref "JP20") (pin "2") (pinfunction "2_2") (pintype "passive"))
      (node (ref "JP20") (pin "3") (pinfunction "3_3") (pintype "passive"))
      (node (ref "JP20") (pin "4") (pinfunction "4_4") (pintype "passive"))
    )
    (net (code "108") (name "Net-(JP21-Pad1)") (class "Default")
      (node (ref "JP21") (pin "1") (pinfunction "1_1") (pintype "passive"))
      (node (ref "JP21") (pin "2") (pinfunction "2_2") (pintype "passive"))
      (node (ref "JP21") (pin "3") (pinfunction "3_3") (pintype "passive"))
      (node (ref "JP21") (pin "4") (pinfunction "4_4") (pintype "passive"))
    )
    (net (code "109") (name "Net-(JP22-Pad1)") (class "Default")
      (node (ref "JP22") (pin "1") (pinfunction "1_1") (pintype "passive"))
      (node (ref "JP23") (pin "1") (pinfunction "1_1") (pintype "passive"))
      (node (ref "JP24") (pin "1") (pinfunction "1_1") (pintype "passive"))
      (node (ref "JP25") (pin "1") (pinfunction "1_1") (pintype "passive"))
      (node (ref "JP26") (pin "1") (pinfunction "1_1") (pintype "passive"))
    )
    (net (code "110") (name "Net-(JP22-Pad2)") (class "Default")
      (node (ref "JP22") (pin "2") (pinfunction "2_2") (pintype "passive"))
      (node (ref "JP23") (pin "2") (pinfunction "2_2") (pintype "passive"))
      (node (ref "JP24") (pin "2") (pinfunction "2_2") (pintype "passive"))
      (node (ref "JP25") (pin "2") (pinfunction "2_2") (pintype "passive"))
      (node (ref "JP26") (pin "2") (pinfunction "2_2") (pintype "passive"))
    )
    (net (code "111") (name "Net-(JP22-Pad3)") (class "Default")
      (node (ref "JP22") (pin "3") (pinfunction "3_3") (pintype "passive"))
      (node (ref "JP23") (pin "3") (pinfunction "3_3") (pintype "passive"))
      (node (ref "JP24") (pin "3") (pinfunction "3_3") (pintype "passive"))
      (node (ref "JP25") (pin "3") (pinfunction "3_3") (pintype "passive"))
      (node (ref "JP26") (pin "3") (pinfunction "3_3") (pintype "passive"))
    )
    (net (code "112") (name "Net-(JP22-Pad4)") (class "Default")
      (node (ref "JP22") (pin "4") (pinfunction "4_4") (pintype "passive"))
      (node (ref "JP23") (pin "4") (pinfunction "4_4") (pintype "passive"))
      (node (ref "JP24") (pin "4") (pinfunction "4_4") (pintype "passive"))
      (node (ref "JP25") (pin "4") (pinfunction "4_4") (pintype "passive"))
      (node (ref "JP26") (pin "4") (pinfunction "4_4") (pintype "passive"))
    )
    (net (code "113") (name "Net-(JP22-Pad5)") (class "Default")
      (node (ref "JP22") (pin "5") (pinfunction "5_5") (pintype "passive"))
      (node (ref "JP23") (pin "5") (pinfunction "5_5") (pintype "passive"))
      (node (ref "JP24") (pin "5") (pinfunction "5_5") (pintype "passive"))
      (node (ref "JP25") (pin "5") (pinfunction "5_5") (pintype "passive"))
      (node (ref "JP26") (pin "5") (pinfunction "5_5") (pintype "passive"))
    )
    (net (code "114") (name "Net-(JP22-Pad6)") (class "Default")
      (node (ref "JP22") (pin "6") (pinfunction "6_6") (pintype "passive"))
      (node (ref "JP23") (pin "6") (pinfunction "6_6") (pintype "passive"))
      (node (ref "JP24") (pin "6") (pinfunction "6_6") (pintype "passive"))
      (node (ref "JP25") (pin "6") (pinfunction "6_6") (pintype "passive"))
      (node (ref "JP26") (pin "6") (pinfunction "6_6") (pintype "passive"))
    )
    (net (code "115") (name "Net-(JP22-Pad7)") (class "Default")
      (node (ref "JP22") (pin "7") (pinfunction "7_7") (pintype "passive"))
      (node (ref "JP23") (pin "7") (pinfunction "7_7") (pintype "passive"))
      (node (ref "JP24") (pin "7") (pinfunction "7_7") (pintype "passive"))
      (node (ref "JP25") (pin "7") (pinfunction "7_7") (pintype "passive"))
      (node (ref "JP26") (pin "7") (pinfunction "7_7") (pintype "passive"))
    )
    (net (code "116") (name "Net-(JP22-Pad8)") (class "Default")
      (node (ref "JP22") (pin "8") (pinfunction "8_8") (pintype "passive"))
      (node (ref "JP23") (pin "8") (pinfunction "8_8") (pintype "passive"))
      (node (ref "JP24") (pin "8") (pinfunction "8_8") (pintype "passive"))
      (node (ref "JP25") (pin "8") (pinfunction "8_8") (pintype "passive"))
      (node (ref "JP26") (pin "8") (pinfunction "8_8") (pintype "passive"))
    )
    (net (code "117") (name "Net-(JP22-Pad9)") (class "Default")
      (node (ref "JP22") (pin "9") (pinfunction "9_9") (pintype "passive"))
      (node (ref "JP23") (pin "9") (pinfunction "9_9") (pintype "passive"))
      (node (ref "JP24") (pin "9") (pinfunction "9_9") (pintype "passive"))
      (node (ref "JP25") (pin "9") (pinfunction "9_9") (pintype "passive"))
      (node (ref "JP26") (pin "9") (pinfunction "9_9") (pintype "passive"))
    )
    (net (code "118") (name "Net-(JP22-Pad10)") (class "Default")
      (node (ref "JP22") (pin "10") (pinfunction "10_10") (pintype "passive"))
      (node (ref "JP23") (pin "10") (pinfunction "10_10") (pintype "passive"))
      (node (ref "JP24") (pin "10") (pinfunction "10_10") (pintype "passive"))
      (node (ref "JP25") (pin "10") (pinfunction "10_10") (pintype "passive"))
      (node (ref "JP26") (pin "10") (pinfunction "10_10") (pintype "passive"))
    )
    (net (code "119") (name "Net-(JP22-Pad11)") (class "Default")
      (node (ref "JP22") (pin "11") (pinfunction "11_11") (pintype "passive"))
      (node (ref "JP23") (pin "11") (pinfunction "11_11") (pintype "passive"))
      (node (ref "JP24") (pin "11") (pinfunction "11_11") (pintype "passive"))
      (node (ref "JP25") (pin "11") (pinfunction "11_11") (pintype "passive"))
      (node (ref "JP26") (pin "11") (pinfunction "11_11") (pintype "passive"))
    )
    (net (code "120") (name "Net-(JP22-Pad12)") (class "Default")
      (node (ref "JP22") (pin "12") (pinfunction "12_12") (pintype "passive"))
      (node (ref "JP23") (pin "12") (pinfunction "12_12") (pintype "passive"))
      (node (ref "JP24") (pin "12") (pinfunction "12_12") (pintype "passive"))
      (node (ref "JP25") (pin "12") (pinfunction "12_12") (pintype "passive"))
      (node (ref "JP26") (pin "12") (pinfunction "12_12") (pintype "passive"))
    )
    (net (code "121") (name "Net-(JP22-Pad13)") (class "Default")
      (node (ref "JP22") (pin "13") (pinfunction "13_13") (pintype "passive"))
      (node (ref "JP23") (pin "13") (pinfunction "13_13") (pintype "passive"))
      (node (ref "JP24") (pin "13") (pinfunction "13_13") (pintype "passive"))
      (node (ref "JP25") (pin "13") (pinfunction "13_13") (pintype "passive"))
      (node (ref "JP26") (pin "13") (pinfunction "13_13") (pintype "passive"))
    )
    (net (code "122") (name "Net-(JP22-Pad14)") (class "Default")
      (node (ref "JP22") (pin "14") (pinfunction "14_14") (pintype "passive"))
      (node (ref "JP23") (pin "14") (pinfunction "14_14") (pintype "passive"))
      (node (ref "JP24") (pin "14") (pinfunction "14_14") (pintype "passive"))
      (node (ref "JP25") (pin "14") (pinfunction "14_14") (pintype "passive"))
      (node (ref "JP26") (pin "14") (pinfunction "14_14") (pintype "passive"))
    )
    (net (code "123") (name "Net-(JP22-Pad15)") (class "Default")
      (node (ref "JP22") (pin "15") (pinfunction "15_15") (pintype "passive"))
      (node (ref "JP23") (pin "15") (pinfunction "15_15") (pintype "passive"))
      (node (ref "JP24") (pin "15") (pinfunction "15_15") (pintype "passive"))
      (node (ref "JP25") (pin "15") (pinfunction "15_15") (pintype "passive"))
      (node (ref "JP26") (pin "15") (pinfunction "15_15") (pintype "passive"))
    )
    (net (code "124") (name "Net-(JP27-Pad1)") (class "Default")
      (node (ref "JP27") (pin "1") (pinfunction "1_1") (pintype "passive"))
      (node (ref "JP27") (pin "2") (pinfunction "2_2") (pintype "passive"))
      (node (ref "JP27") (pin "3") (pinfunction "3_3") (pintype "passive"))
      (node (ref "JP27") (pin "4") (pinfunction "4_4") (pintype "passive"))
    )
    (net (code "125") (name "Net-(JP28-Pad1)") (class "Default")
      (node (ref "JP28") (pin "1") (pinfunction "1_1") (pintype "passive"))
      (node (ref "JP28") (pin "2") (pinfunction "2_2") (pintype "passive"))
      (node (ref "JP28") (pin "3") (pinfunction "3_3") (pintype "passive"))
      (node (ref "JP28") (pin "4") (pinfunction "4_4") (pintype "passive"))
    )
    (net (code "126") (name "Net-(JP29-Pad1)") (class "Default")
      (node (ref "JP29") (pin "1") (pinfunction "1_1") (pintype "passive"))
      (node (ref "JP29") (pin "2") (pinfunction "2_2") (pintype "passive"))
      (node (ref "JP29") (pin "3") (pinfunction "3_3") (pintype "passive"))
      (node (ref "JP29") (pin "4") (pinfunction "4_4") (pintype "passive"))
    )
    (net (code "127") (name "Net-(JP30-Pad1)") (class "Default")
      (node (ref "JP30") (pin "1") (pinfunction "1_1") (pintype "passive"))
      (node (ref "JP30") (pin "2") (pinfunction "2_2") (pintype "passive"))
      (node (ref "JP30") (pin "3") (pinfunction "3_3") (pintype "passive"))
      (node (ref "JP30") (pin "4") (pinfunction "4_4") (pintype "passive"))
    )
    (net (code "128") (name "unconnected-(IC1A-Q6-Pad2)") (class "Default")
      (node (ref "IC1") (pin "2") (pinfunction "Q6_2") (pintype "output"))
    )
    (net (code "129") (name "unconnected-(IC1A-Q7-Pad12)") (class "Default")
      (node (ref "IC1") (pin "12") (pinfunction "Q7_12") (pintype "output"))
    )
    (net (code "130") (name "unconnected-(IC2A-Q6-Pad2)") (class "Default")
      (node (ref "IC2") (pin "2") (pinfunction "Q6_2") (pintype "output"))
    )
    (net (code "131") (name "unconnected-(IC2A-Q7-Pad12)") (class "Default")
      (node (ref "IC2") (pin "12") (pinfunction "Q7_12") (pintype "output"))
    )
    (net (code "132") (name "unconnected-(IC3A-Q6-Pad2)") (class "Default")
      (node (ref "IC3") (pin "2") (pinfunction "Q6_2") (pintype "output"))
    )
    (net (code "133") (name "unconnected-(IC3A-Q7-Pad12)") (class "Default")
      (node (ref "IC3") (pin "12") (pinfunction "Q7_12") (pintype "output"))
    )
    (net (code "134") (name "unconnected-(IC4A-Q6-Pad2)") (class "Default")
      (node (ref "IC4") (pin "2") (pinfunction "Q6_2") (pintype "output"))
    )
    (net (code "135") (name "unconnected-(IC4A-Q7-Pad12)") (class "Default")
      (node (ref "IC4") (pin "12") (pinfunction "Q7_12") (pintype "output"))
    )
    (net (code "136") (name "unconnected-(IC5A-Q6-Pad2)") (class "Default")
      (node (ref "IC5") (pin "2") (pinfunction "Q6_2") (pintype "output"))
    )
    (net (code "137") (name "unconnected-(IC5A-Q7-Pad12)") (class "Default")
      (node (ref "IC5") (pin "12") (pinfunction "Q7_12") (pintype "output"))
    )
  )
)
